# leg_controller.net
KiCad netlist of a schematic drawn in EAGLE
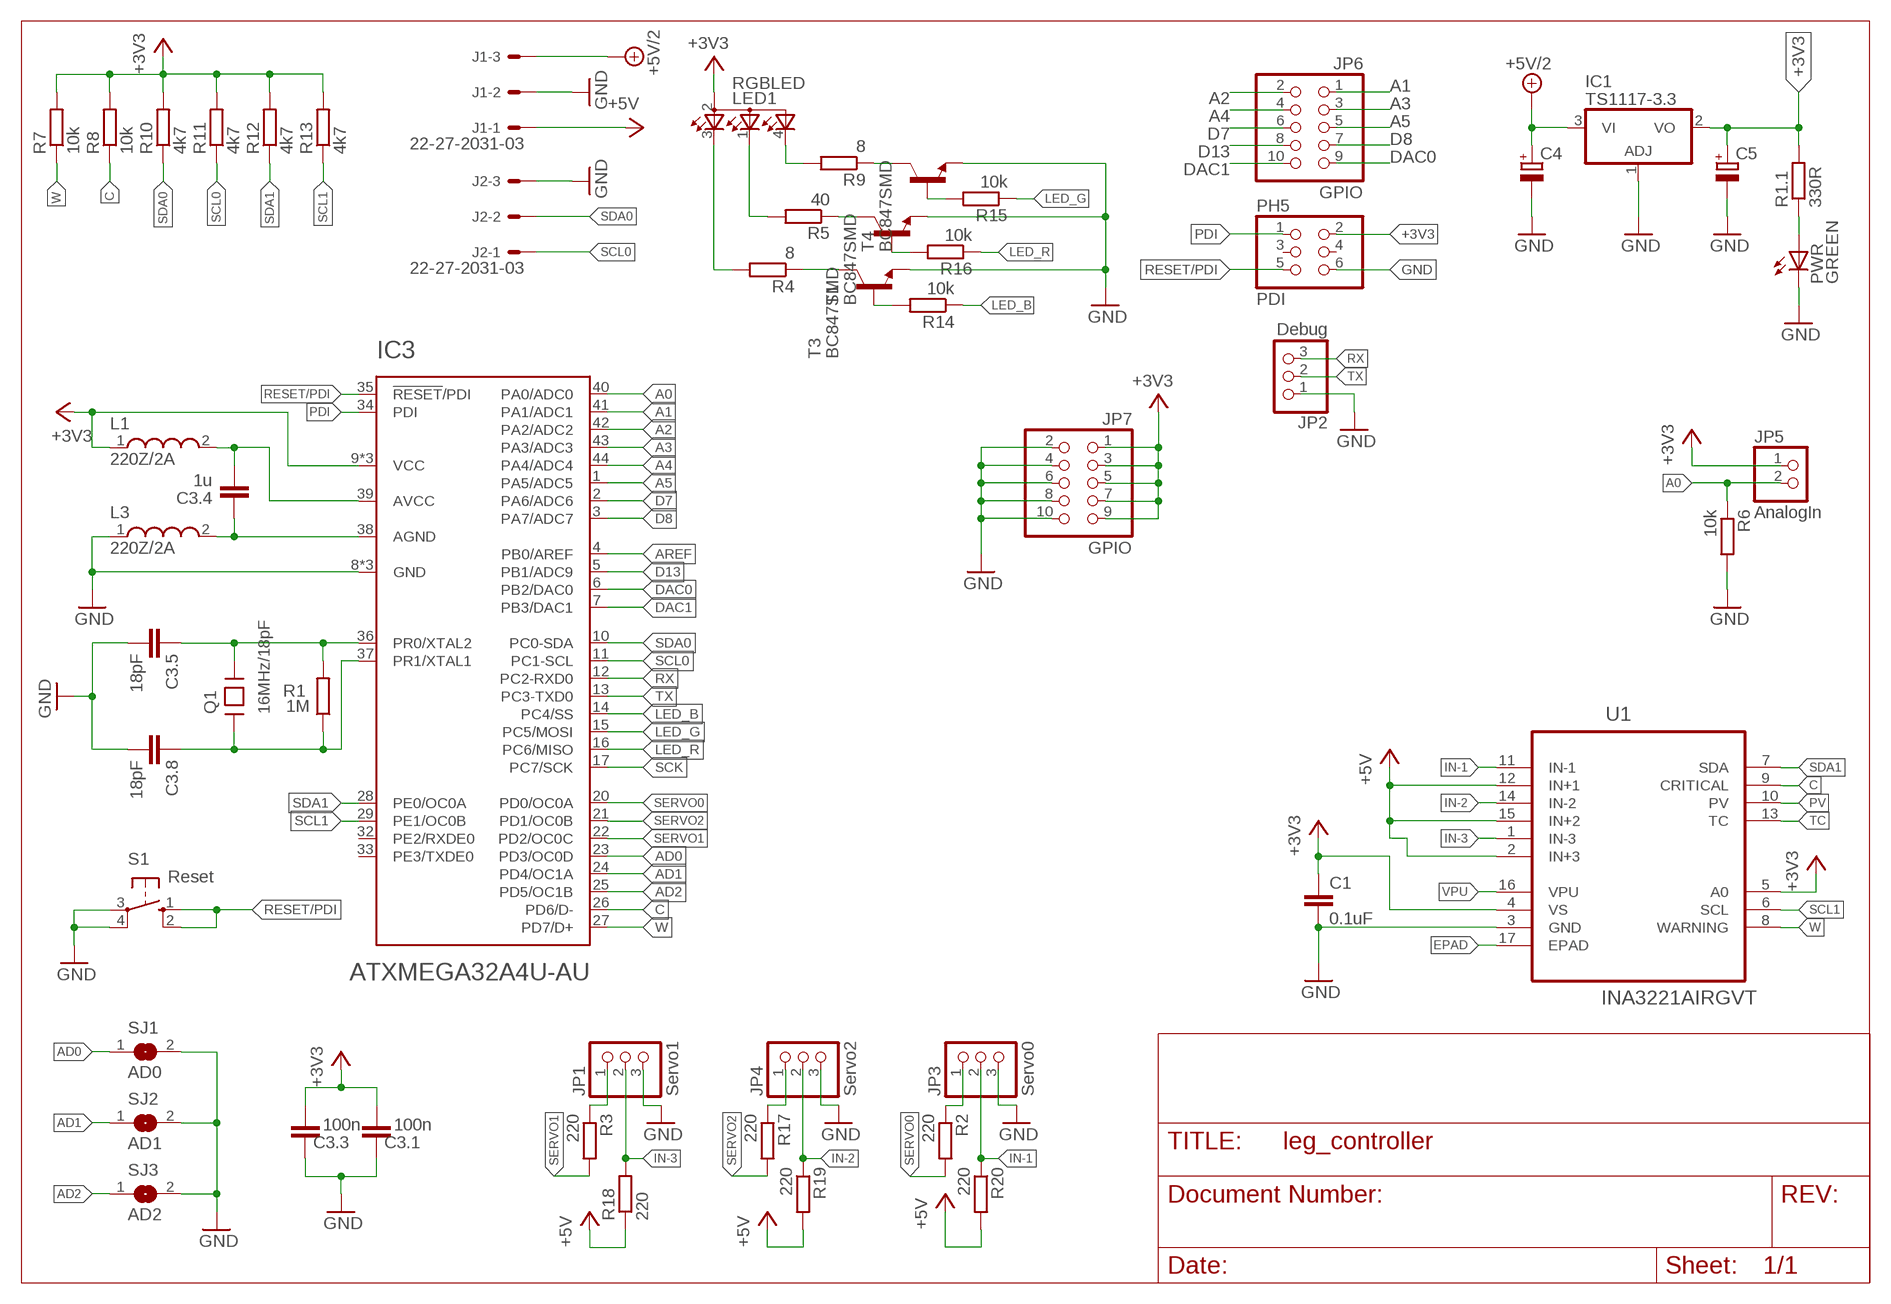
[diagram p0: schematic, sheet 1]

(export (version "E")
  (design (tool "Eeschema 10.0.6"))
  (components
    (comp (ref "C1")
      (value "0.1uF")
      (footprint "eagle-import:C0805")
      (libsource (lib "eagle-import") (part "C-EUC0805"))
    )
    (comp (ref "C3.1")
      (value "100n")
      (footprint "eagle-import:C0805K")
      (libsource (lib "eagle-import") (part "C-EUC0805K"))
    )
    (comp (ref "C3.3")
      (value "100n")
      (footprint "eagle-import:C0805K")
      (libsource (lib "eagle-import") (part "C-EUC0805K"))
    )
    (comp (ref "C3.4")
      (value "1u")
      (footprint "eagle-import:C0805K")
      (libsource (lib "eagle-import") (part "C-EUC0805K"))
    )
    (comp (ref "C3.5")
      (value "18pF")
      (footprint "eagle-import:C0805K")
      (libsource (lib "eagle-import") (part "C-EUC0805K"))
    )
    (comp (ref "C3.8")
      (value "18pF")
      (footprint "eagle-import:C0805K")
      (libsource (lib "eagle-import") (part "C-EUC0805K"))
    )
    (comp (ref "C4")
      (value "CPOL-EUSMCA")
      (footprint "eagle-import:SMC_A")
      (libsource (lib "eagle-import") (part "CPOL-EUSMCA"))
    )
    (comp (ref "C5")
      (value "CPOL-EUSMCA")
      (footprint "eagle-import:SMC_A")
      (libsource (lib "eagle-import") (part "CPOL-EUSMCA"))
    )
    (comp (ref "IC1")
      (value "TS1117-3.3")
      (footprint "eagle-import:DPACK")
      (libsource (lib "eagle-import") (part "MC33269?D-3.3"))
    )
    (comp (ref "IC3")
      (value "ATXMEGA32A4U-AU")
      (footprint "eagle-import:TQFP-44A-44")
      (libsource (lib "eagle-import") (part "ATXMEGA32A4U-AU"))
    )
    (comp (ref "J1")
      (value "22-27-2031-03")
      (footprint "eagle-import:6410-03")
      (libsource (lib "eagle-import") (part "22-?-0327-2031"))
    )
    (comp (ref "J2")
      (value "22-27-2031-03")
      (footprint "eagle-import:6410-03")
      (libsource (lib "eagle-import") (part "22-?-0327-2031"))
    )
    (comp (ref "JP1")
      (value "Servo1")
      (footprint "eagle-import:1X03")
      (libsource (lib "eagle-import") (part "PINHD-1X3"))
    )
    (comp (ref "JP2")
      (value "Debug")
      (footprint "eagle-import:1X03")
      (libsource (lib "eagle-import") (part "pinhead_NEW_PINHD-1X3"))
    )
    (comp (ref "JP3")
      (value "Servo0")
      (footprint "eagle-import:1X03")
      (libsource (lib "eagle-import") (part "PINHD-1X3"))
    )
    (comp (ref "JP4")
      (value "Servo2")
      (footprint "eagle-import:1X03")
      (libsource (lib "eagle-import") (part "PINHD-1X3"))
    )
    (comp (ref "JP5")
      (value "AnalogIn")
      (footprint "eagle-import:1X02")
      (libsource (lib "eagle-import") (part "PINHD-1X2"))
    )
    (comp (ref "JP6")
      (value "GPIO")
      (footprint "eagle-import:2X05")
      (libsource (lib "eagle-import") (part "PINHD-2X5"))
    )
    (comp (ref "JP7")
      (value "GPIO")
      (footprint "eagle-import:2X05")
      (libsource (lib "eagle-import") (part "PINHD-2X5"))
    )
    (comp (ref "L1")
      (value "220Z/2A")
      (footprint "eagle-import:WE-CBF_0805(W=3.0)")
      (libsource (lib "eagle-import") (part "WE-CBF_0805(WB/HS)"))
    )
    (comp (ref "L3")
      (value "220Z/2A")
      (footprint "eagle-import:WE-CBF_0805(W=3.0)")
      (libsource (lib "eagle-import") (part "WE-CBF_0805(WB/HS)"))
    )
    (comp (ref "LED1")
      (value "RGBLED")
      (footprint "eagle-import:P-LCC4-RGB")
      (libsource (lib "eagle-import") (part "RGBLED"))
    )
    (comp (ref "PH5")
      (value "PDI")
      (footprint "eagle-import:2X03")
      (libsource (lib "eagle-import") (part "PINHD-2X3"))
    )
    (comp (ref "PWR")
      (value "GREEN")
      (footprint "eagle-import:CHIP-LED0805")
      (libsource (lib "eagle-import") (part "LEDCHIP-LED0805"))
    )
    (comp (ref "Q1")
      (value "16MHz/18pF")
      (footprint "eagle-import:CRYSTAL-ABRACON-ABM3-SMD")
      (libsource (lib "eagle-import") (part "CRYSTAL-ABRACON-ABM3-SMD"))
    )
    (comp (ref "R1")
      (value "1M")
      (footprint "eagle-import:R0805")
      (libsource (lib "eagle-import") (part "R-EU_R0805"))
    )
    (comp (ref "R1.1")
      (value "330R")
      (footprint "eagle-import:R0805")
      (libsource (lib "eagle-import") (part "R-EU_R0805"))
    )
    (comp (ref "R2")
      (value "220")
      (footprint "eagle-import:R0805")
      (libsource (lib "eagle-import") (part "R-EU_R0805"))
    )
    (comp (ref "R3")
      (value "220")
      (footprint "eagle-import:R0805")
      (libsource (lib "eagle-import") (part "R-EU_R0805"))
    )
    (comp (ref "R4")
      (value "8")
      (footprint "eagle-import:R0805")
      (libsource (lib "eagle-import") (part "R-EU_R0805"))
    )
    (comp (ref "R5")
      (value "40")
      (footprint "eagle-import:R0805")
      (libsource (lib "eagle-import") (part "R-EU_R0805"))
    )
    (comp (ref "R6")
      (value "10k")
      (footprint "eagle-import:M0805")
      (libsource (lib "eagle-import") (part "R-EU_M0805"))
    )
    (comp (ref "R7")
      (value "10k")
      (footprint "eagle-import:R0805")
      (libsource (lib "eagle-import") (part "R-EU_R0805"))
    )
    (comp (ref "R8")
      (value "10k")
      (footprint "eagle-import:R0805")
      (libsource (lib "eagle-import") (part "R-EU_R0805"))
    )
    (comp (ref "R9")
      (value "8")
      (footprint "eagle-import:R0805")
      (libsource (lib "eagle-import") (part "R-EU_R0805"))
    )
    (comp (ref "R10")
      (value "4k7")
      (footprint "eagle-import:R0805")
      (libsource (lib "eagle-import") (part "R-EU_R0805"))
    )
    (comp (ref "R11")
      (value "4k7")
      (footprint "eagle-import:R0805")
      (libsource (lib "eagle-import") (part "R-EU_R0805"))
    )
    (comp (ref "R12")
      (value "4k7")
      (footprint "eagle-import:R0805")
      (libsource (lib "eagle-import") (part "R-EU_R0805"))
    )
    (comp (ref "R13")
      (value "4k7")
      (footprint "eagle-import:R0805")
      (libsource (lib "eagle-import") (part "R-EU_R0805"))
    )
    (comp (ref "R14")
      (value "10k")
      (footprint "eagle-import:R0805")
      (libsource (lib "eagle-import") (part "R-EU_R0805"))
    )
    (comp (ref "R15")
      (value "10k")
      (footprint "eagle-import:R0805")
      (libsource (lib "eagle-import") (part "R-EU_R0805"))
    )
    (comp (ref "R16")
      (value "10k")
      (footprint "eagle-import:R0805")
      (libsource (lib "eagle-import") (part "R-EU_R0805"))
    )
    (comp (ref "R17")
      (value "220")
      (footprint "eagle-import:R0805")
      (libsource (lib "eagle-import") (part "R-EU_R0805"))
    )
    (comp (ref "R18")
      (value "220")
      (footprint "eagle-import:R1206")
      (libsource (lib "eagle-import") (part "R-EU_R1206"))
    )
    (comp (ref "R19")
      (value "220")
      (footprint "eagle-import:R1206")
      (libsource (lib "eagle-import") (part "R-EU_R1206"))
    )
    (comp (ref "R20")
      (value "220")
      (footprint "eagle-import:R1206")
      (libsource (lib "eagle-import") (part "R-EU_R1206"))
    )
    (comp (ref "S1")
      (value "Reset")
      (footprint "eagle-import:B3F-10XX")
      (fields (field (name "MPN") "B3F-1000"))
      (libsource (lib "eagle-import") (part "10-XX"))
    )
    (comp (ref "SJ1")
      (value "AD0")
      (footprint "eagle-import:SJ")
      (libsource (lib "eagle-import") (part "SJ"))
    )
    (comp (ref "SJ2")
      (value "AD1")
      (footprint "eagle-import:SJ")
      (libsource (lib "eagle-import") (part "SJ"))
    )
    (comp (ref "SJ3")
      (value "AD2")
      (footprint "eagle-import:SJ")
      (libsource (lib "eagle-import") (part "SJ"))
    )
    (comp (ref "T1")
      (value "BC847SMD")
      (footprint "eagle-import:SOT23")
      (libsource (lib "eagle-import") (part "BC847SMD"))
    )
    (comp (ref "T3")
      (value "BC847SMD")
      (footprint "eagle-import:SOT23")
      (libsource (lib "eagle-import") (part "BC847SMD"))
    )
    (comp (ref "T4")
      (value "BC847SMD")
      (footprint "eagle-import:SOT23")
      (libsource (lib "eagle-import") (part "BC847SMD"))
    )
    (comp (ref "U1")
      (value "INA3221AIRGVT")
      (footprint "eagle-import:QFN65P400X400X80-17N")
      (libsource (lib "eagle-import") (part "INA3221AIRGVT"))
    )
  )
  (nets
    (net (code "1") (name "+3V3") (class "Default")
      (node (ref "C1") (pin "1") (pinfunction "1_1") (pintype "passive"))
      (node (ref "C3.1") (pin "1") (pinfunction "1_1") (pintype "passive"))
      (node (ref "C3.3") (pin "1") (pinfunction "1_1") (pintype "passive"))
      (node (ref "C5") (pin "+") (pinfunction "+_+") (pintype "passive"))
      (node (ref "IC1") (pin "2") (pinfunction "VO_2") (pintype "passive"))
      (node (ref "IC3") (pin "19") (pinfunction "VCC_19") (pintype "power_in"))
      (node (ref "IC3") (pin "31") (pinfunction "VCC_31") (pintype "power_in"))
      (node (ref "IC3") (pin "9") (pinfunction "VCC_9") (pintype "power_in"))
      (node (ref "JP5") (pin "1") (pinfunction "1_1") (pintype "passive"))
      (node (ref "JP7") (pin "1") (pinfunction "1_1") (pintype "passive"))
      (node (ref "JP7") (pin "3") (pinfunction "3_3") (pintype "passive"))
      (node (ref "JP7") (pin "5") (pinfunction "5_5") (pintype "passive"))
      (node (ref "JP7") (pin "7") (pinfunction "7_7") (pintype "passive"))
      (node (ref "JP7") (pin "9") (pinfunction "9_9") (pintype "passive"))
      (node (ref "L1") (pin "1") (pinfunction "1_1") (pintype "passive"))
      (node (ref "LED1") (pin "2") (pinfunction "A2_2") (pintype "passive"))
      (node (ref "PH5") (pin "2") (pinfunction "2_2") (pintype "passive"))
      (node (ref "R1.1") (pin "2") (pinfunction "2_2") (pintype "passive"))
      (node (ref "R10") (pin "2") (pinfunction "2_2") (pintype "passive"))
      (node (ref "R11") (pin "2") (pinfunction "2_2") (pintype "passive"))
      (node (ref "R12") (pin "2") (pinfunction "2_2") (pintype "passive"))
      (node (ref "R13") (pin "2") (pinfunction "2_2") (pintype "passive"))
      (node (ref "R7") (pin "2") (pinfunction "2_2") (pintype "passive"))
      (node (ref "R8") (pin "2") (pinfunction "2_2") (pintype "passive"))
      (node (ref "U1") (pin "4") (pinfunction "VS_4") (pintype "power_in"))
      (node (ref "U1") (pin "5") (pinfunction "A0_5") (pintype "input"))
    )
    (net (code "2") (name "+5V") (class "Default")
      (node (ref "J1") (pin "1") (pinfunction "S_1") (pintype "passive"))
      (node (ref "R18") (pin "1") (pinfunction "1_1") (pintype "passive"))
      (node (ref "R19") (pin "2") (pinfunction "2_2") (pintype "passive"))
      (node (ref "R20") (pin "2") (pinfunction "2_2") (pintype "passive"))
      (node (ref "U1") (pin "12") (pinfunction "IN+1_12") (pintype "input"))
      (node (ref "U1") (pin "15") (pinfunction "IN+2_15") (pintype "input"))
      (node (ref "U1") (pin "2") (pinfunction "IN+3_2") (pintype "input"))
    )
    (net (code "3") (name "+5V{slash}2") (class "Default")
      (node (ref "C4") (pin "+") (pinfunction "+_+") (pintype "passive"))
      (node (ref "IC1") (pin "3") (pinfunction "VI_3") (pintype "input"))
      (node (ref "J1") (pin "3") (pinfunction "S_3") (pintype "passive"))
    )
    (net (code "4") (name "A0") (class "Default")
      (node (ref "IC3") (pin "40") (pinfunction "PA0/ADC0_40") (pintype "bidirectional"))
      (node (ref "JP5") (pin "2") (pinfunction "2_2") (pintype "passive"))
      (node (ref "R6") (pin "1") (pinfunction "1_1") (pintype "passive"))
    )
    (net (code "5") (name "A1") (class "Default")
      (node (ref "IC3") (pin "41") (pinfunction "PA1/ADC1_41") (pintype "bidirectional"))
      (node (ref "JP6") (pin "1") (pinfunction "1_1") (pintype "passive"))
    )
    (net (code "6") (name "A2") (class "Default")
      (node (ref "IC3") (pin "42") (pinfunction "PA2/ADC2_42") (pintype "bidirectional"))
      (node (ref "JP6") (pin "2") (pinfunction "2_2") (pintype "passive"))
    )
    (net (code "7") (name "A3") (class "Default")
      (node (ref "IC3") (pin "43") (pinfunction "PA3/ADC3_43") (pintype "bidirectional"))
      (node (ref "JP6") (pin "3") (pinfunction "3_3") (pintype "passive"))
    )
    (net (code "8") (name "A4") (class "Default")
      (node (ref "IC3") (pin "44") (pinfunction "PA4/ADC4_44") (pintype "bidirectional"))
      (node (ref "JP6") (pin "4") (pinfunction "4_4") (pintype "passive"))
    )
    (net (code "9") (name "A5") (class "Default")
      (node (ref "IC3") (pin "1") (pinfunction "PA5/ADC5_1") (pintype "bidirectional"))
      (node (ref "JP6") (pin "5") (pinfunction "5_5") (pintype "passive"))
    )
    (net (code "10") (name "AD0") (class "Default")
      (node (ref "IC3") (pin "23") (pinfunction "PD3/OC0D_23") (pintype "bidirectional"))
      (node (ref "SJ1") (pin "1") (pinfunction "1_1") (pintype "passive"))
    )
    (net (code "11") (name "AD1") (class "Default")
      (node (ref "IC3") (pin "24") (pinfunction "PD4/OC1A_24") (pintype "bidirectional"))
      (node (ref "SJ2") (pin "1") (pinfunction "1_1") (pintype "passive"))
    )
    (net (code "12") (name "AD2") (class "Default")
      (node (ref "IC3") (pin "25") (pinfunction "PD5/OC1B_25") (pintype "bidirectional"))
      (node (ref "SJ3") (pin "1") (pinfunction "1_1") (pintype "passive"))
    )
    (net (code "13") (name "AREF") (class "Default")
      (node (ref "IC3") (pin "4") (pinfunction "PB0/AREF_4") (pintype "bidirectional"))
    )
    (net (code "14") (name "C") (class "Default")
      (node (ref "IC3") (pin "26") (pinfunction "PD6/D-_26") (pintype "bidirectional"))
      (node (ref "R8") (pin "1") (pinfunction "1_1") (pintype "passive"))
      (node (ref "U1") (pin "9") (pinfunction "CRITICAL_9") (pintype "output"))
    )
    (net (code "15") (name "D7") (class "Default")
      (node (ref "IC3") (pin "2") (pinfunction "PA6/ADC6_2") (pintype "bidirectional"))
      (node (ref "JP6") (pin "6") (pinfunction "6_6") (pintype "passive"))
    )
    (net (code "16") (name "D8") (class "Default")
      (node (ref "IC3") (pin "3") (pinfunction "PA7/ADC7_3") (pintype "bidirectional"))
      (node (ref "JP6") (pin "7") (pinfunction "7_7") (pintype "passive"))
    )
    (net (code "17") (name "D13") (class "Default")
      (node (ref "IC3") (pin "5") (pinfunction "PB1/ADC9_5") (pintype "bidirectional"))
      (node (ref "JP6") (pin "8") (pinfunction "8_8") (pintype "passive"))
    )
    (net (code "18") (name "DAC0") (class "Default")
      (node (ref "IC3") (pin "6") (pinfunction "PB2/DAC0_6") (pintype "bidirectional"))
      (node (ref "JP6") (pin "9") (pinfunction "9_9") (pintype "passive"))
    )
    (net (code "19") (name "DAC1") (class "Default")
      (node (ref "IC3") (pin "7") (pinfunction "PB3/DAC1_7") (pintype "bidirectional"))
      (node (ref "JP6") (pin "10") (pinfunction "10_10") (pintype "passive"))
    )
    (net (code "20") (name "EPAD") (class "Default")
      (node (ref "U1") (pin "17") (pinfunction "EPAD_17") (pintype "passive"))
    )
    (net (code "21") (name "GND") (class "Default")
      (node (ref "C1") (pin "2") (pinfunction "2_2") (pintype "passive"))
      (node (ref "C3.1") (pin "2") (pinfunction "2_2") (pintype "passive"))
      (node (ref "C3.3") (pin "2") (pinfunction "2_2") (pintype "passive"))
      (node (ref "C3.5") (pin "2") (pinfunction "2_2") (pintype "passive"))
      (node (ref "C3.8") (pin "2") (pinfunction "2_2") (pintype "passive"))
      (node (ref "C4") (pin "-") (pinfunction "-_-") (pintype "passive"))
      (node (ref "C5") (pin "-") (pinfunction "-_-") (pintype "passive"))
      (node (ref "IC1") (pin "1") (pinfunction "ADJ_1") (pintype "input"))
      (node (ref "IC3") (pin "18") (pinfunction "GND_18") (pintype "power_in"))
      (node (ref "IC3") (pin "30") (pinfunction "GND_30") (pintype "power_in"))
      (node (ref "IC3") (pin "8") (pinfunction "GND_8") (pintype "power_in"))
      (node (ref "J1") (pin "2") (pinfunction "S_2") (pintype "passive"))
      (node (ref "J2") (pin "3") (pinfunction "S_3") (pintype "passive"))
      (node (ref "JP1") (pin "3") (pinfunction "3_3") (pintype "passive"))
      (node (ref "JP2") (pin "1") (pinfunction "1_1") (pintype "passive"))
      (node (ref "JP3") (pin "3") (pinfunction "3_3") (pintype "passive"))
      (node (ref "JP4") (pin "3") (pinfunction "3_3") (pintype "passive"))
      (node (ref "JP7") (pin "10") (pinfunction "10_10") (pintype "passive"))
      (node (ref "JP7") (pin "2") (pinfunction "2_2") (pintype "passive"))
      (node (ref "JP7") (pin "4") (pinfunction "4_4") (pintype "passive"))
      (node (ref "JP7") (pin "6") (pinfunction "6_6") (pintype "passive"))
      (node (ref "JP7") (pin "8") (pinfunction "8_8") (pintype "passive"))
      (node (ref "L3") (pin "1") (pinfunction "1_1") (pintype "passive"))
      (node (ref "PH5") (pin "6") (pinfunction "6_6") (pintype "passive"))
      (node (ref "PWR") (pin "C") (pinfunction "C_C") (pintype "passive"))
      (node (ref "R6") (pin "2") (pinfunction "2_2") (pintype "passive"))
      (node (ref "S1") (pin "3") (pinfunction "P_3") (pintype "passive"))
      (node (ref "S1") (pin "4") (pinfunction "P1_4") (pintype "passive"))
      (node (ref "SJ1") (pin "2") (pinfunction "2_2") (pintype "passive"))
      (node (ref "SJ2") (pin "2") (pinfunction "2_2") (pintype "passive"))
      (node (ref "SJ3") (pin "2") (pinfunction "2_2") (pintype "passive"))
      (node (ref "T1") (pin "2") (pinfunction "E_2") (pintype "passive"))
      (node (ref "T3") (pin "2") (pinfunction "E_2") (pintype "passive"))
      (node (ref "T4") (pin "2") (pinfunction "E_2") (pintype "passive"))
      (node (ref "U1") (pin "3") (pinfunction "GND_3") (pintype "passive"))
    )
    (net (code "22") (name "IN-1") (class "Default")
      (node (ref "JP3") (pin "2") (pinfunction "2_2") (pintype "passive"))
      (node (ref "R20") (pin "1") (pinfunction "1_1") (pintype "passive"))
      (node (ref "U1") (pin "11") (pinfunction "IN-1_11") (pintype "input"))
    )
    (net (code "23") (name "IN-2") (class "Default")
      (node (ref "JP4") (pin "2") (pinfunction "2_2") (pintype "passive"))
      (node (ref "R19") (pin "1") (pinfunction "1_1") (pintype "passive"))
      (node (ref "U1") (pin "14") (pinfunction "IN-2_14") (pintype "input"))
    )
    (net (code "24") (name "IN-3") (class "Default")
      (node (ref "JP1") (pin "2") (pinfunction "2_2") (pintype "passive"))
      (node (ref "R18") (pin "2") (pinfunction "2_2") (pintype "passive"))
      (node (ref "U1") (pin "1") (pinfunction "IN-3_1") (pintype "input"))
    )
    (net (code "25") (name "LED_B") (class "Default")
      (node (ref "IC3") (pin "14") (pinfunction "PC4/SS_14") (pintype "bidirectional"))
      (node (ref "R14") (pin "1") (pinfunction "1_1") (pintype "passive"))
    )
    (net (code "26") (name "LED_G") (class "Default")
      (node (ref "IC3") (pin "15") (pinfunction "PC5/MOSI_15") (pintype "bidirectional"))
      (node (ref "R15") (pin "1") (pinfunction "1_1") (pintype "passive"))
    )
    (net (code "27") (name "LED_R") (class "Default")
      (node (ref "IC3") (pin "16") (pinfunction "PC6/MISO_16") (pintype "bidirectional"))
      (node (ref "R16") (pin "1") (pinfunction "1_1") (pintype "passive"))
    )
    (net (code "28") (name "Net-(IC3-AGND)") (class "Default")
      (node (ref "C3.4") (pin "2") (pinfunction "2_2") (pintype "passive"))
      (node (ref "IC3") (pin "38") (pinfunction "AGND_38") (pintype "power_in"))
      (node (ref "L3") (pin "2") (pinfunction "2_2") (pintype "passive"))
    )
    (net (code "29") (name "Net-(IC3-AVCC)") (class "Default")
      (node (ref "C3.4") (pin "1") (pinfunction "1_1") (pintype "passive"))
      (node (ref "IC3") (pin "39") (pinfunction "AVCC_39") (pintype "power_in"))
      (node (ref "L1") (pin "2") (pinfunction "2_2") (pintype "passive"))
    )
    (net (code "30") (name "Net-(IC3-PR0{slash}XTAL2)") (class "Default")
      (node (ref "C3.5") (pin "1") (pinfunction "1_1") (pintype "passive"))
      (node (ref "IC3") (pin "36") (pinfunction "PR0/XTAL2_36") (pintype "bidirectional"))
      (node (ref "Q1") (pin "P$2") (pinfunction "P$2_P$2") (pintype "bidirectional"))
      (node (ref "R1") (pin "2") (pinfunction "2_2") (pintype "passive"))
    )
    (net (code "31") (name "Net-(IC3-PR1{slash}XTAL1)") (class "Default")
      (node (ref "C3.8") (pin "1") (pinfunction "1_1") (pintype "passive"))
      (node (ref "IC3") (pin "37") (pinfunction "PR1/XTAL1_37") (pintype "bidirectional"))
      (node (ref "Q1") (pin "P$1") (pinfunction "P$1_P$1") (pintype "bidirectional"))
      (node (ref "R1") (pin "1") (pinfunction "1_1") (pintype "passive"))
    )
    (net (code "32") (name "Net-(JP1-Pad1)") (class "Default")
      (node (ref "JP1") (pin "1") (pinfunction "1_1") (pintype "passive"))
      (node (ref "R3") (pin "1") (pinfunction "1_1") (pintype "passive"))
    )
    (net (code "33") (name "Net-(JP3-Pad1)") (class "Default")
      (node (ref "JP3") (pin "1") (pinfunction "1_1") (pintype "passive"))
      (node (ref "R2") (pin "1") (pinfunction "1_1") (pintype "passive"))
    )
    (net (code "34") (name "Net-(JP4-Pad1)") (class "Default")
      (node (ref "JP4") (pin "1") (pinfunction "1_1") (pintype "passive"))
      (node (ref "R17") (pin "1") (pinfunction "1_1") (pintype "passive"))
    )
    (net (code "35") (name "Net-(LED1-CBLUE)") (class "Default")
      (node (ref "LED1") (pin "1") (pinfunction "CBLUE_1") (pintype "passive"))
      (node (ref "R5") (pin "2") (pinfunction "2_2") (pintype "passive"))
    )
    (net (code "36") (name "Net-(LED1-CGREEN)") (class "Default")
      (node (ref "LED1") (pin "4") (pinfunction "CGREEN_4") (pintype "passive"))
      (node (ref "R9") (pin "2") (pinfunction "2_2") (pintype "passive"))
    )
    (net (code "37") (name "Net-(LED1-CRED)") (class "Default")
      (node (ref "LED1") (pin "3") (pinfunction "CRED_3") (pintype "passive"))
      (node (ref "R4") (pin "2") (pinfunction "2_2") (pintype "passive"))
    )
    (net (code "38") (name "Net-(PWR-PadA)") (class "Default")
      (node (ref "PWR") (pin "A") (pinfunction "A_A") (pintype "passive"))
      (node (ref "R1.1") (pin "1") (pinfunction "1_1") (pintype "passive"))
    )
    (net (code "39") (name "Net-(T1-B)") (class "Default")
      (node (ref "R16") (pin "2") (pinfunction "2_2") (pintype "passive"))
      (node (ref "T1") (pin "1") (pinfunction "B_1") (pintype "passive"))
    )
    (net (code "40") (name "Net-(T1-C)") (class "Default")
      (node (ref "R5") (pin "1") (pinfunction "1_1") (pintype "passive"))
      (node (ref "T1") (pin "3") (pinfunction "C_3") (pintype "passive"))
    )
    (net (code "41") (name "Net-(T3-B)") (class "Default")
      (node (ref "R14") (pin "2") (pinfunction "2_2") (pintype "passive"))
      (node (ref "T3") (pin "1") (pinfunction "B_1") (pintype "passive"))
    )
    (net (code "42") (name "Net-(T3-C)") (class "Default")
      (node (ref "R4") (pin "1") (pinfunction "1_1") (pintype "passive"))
      (node (ref "T3") (pin "3") (pinfunction "C_3") (pintype "passive"))
    )
    (net (code "43") (name "Net-(T4-B)") (class "Default")
      (node (ref "R15") (pin "2") (pinfunction "2_2") (pintype "passive"))
      (node (ref "T4") (pin "1") (pinfunction "B_1") (pintype "passive"))
    )
    (net (code "44") (name "Net-(T4-C)") (class "Default")
      (node (ref "R9") (pin "1") (pinfunction "1_1") (pintype "passive"))
      (node (ref "T4") (pin "3") (pinfunction "C_3") (pintype "passive"))
    )
    (net (code "45") (name "PDI") (class "Default")
      (node (ref "IC3") (pin "34") (pinfunction "PDI_34") (pintype "bidirectional"))
      (node (ref "PH5") (pin "1") (pinfunction "1_1") (pintype "passive"))
    )
    (net (code "46") (name "PV") (class "Default")
      (node (ref "U1") (pin "10") (pinfunction "PV_10") (pintype "output"))
    )
    (net (code "47") (name "RESET{slash}PDI") (class "Default")
      (node (ref "IC3") (pin "35") (pinfunction "~{RESET}/PDI_35") (pintype "bidirectional"))
      (node (ref "PH5") (pin "5") (pinfunction "5_5") (pintype "passive"))
      (node (ref "S1") (pin "1") (pinfunction "S_1") (pintype "passive"))
      (node (ref "S1") (pin "2") (pinfunction "S1_2") (pintype "passive"))
    )
    (net (code "48") (name "RX") (class "Default")
      (node (ref "IC3") (pin "12") (pinfunction "PC2-RXD0_12") (pintype "bidirectional"))
      (node (ref "JP2") (pin "3") (pinfunction "3_3") (pintype "passive"))
    )
    (net (code "49") (name "SCK") (class "Default")
      (node (ref "IC3") (pin "17") (pinfunction "PC7/SCK_17") (pintype "bidirectional"))
    )
    (net (code "50") (name "SCL0") (class "Default")
      (node (ref "IC3") (pin "11") (pinfunction "PC1-SCL_11") (pintype "bidirectional"))
      (node (ref "J2") (pin "1") (pinfunction "S_1") (pintype "passive"))
      (node (ref "R11") (pin "1") (pinfunction "1_1") (pintype "passive"))
    )
    (net (code "51") (name "SCL1") (class "Default")
      (node (ref "IC3") (pin "29") (pinfunction "PE1/OC0B_29") (pintype "bidirectional"))
      (node (ref "R13") (pin "1") (pinfunction "1_1") (pintype "passive"))
      (node (ref "U1") (pin "6") (pinfunction "SCL_6") (pintype "input"))
    )
    (net (code "52") (name "SDA0") (class "Default")
      (node (ref "IC3") (pin "10") (pinfunction "PC0-SDA_10") (pintype "bidirectional"))
      (node (ref "J2") (pin "2") (pinfunction "S_2") (pintype "passive"))
      (node (ref "R10") (pin "1") (pinfunction "1_1") (pintype "passive"))
    )
    (net (code "53") (name "SDA1") (class "Default")
      (node (ref "IC3") (pin "28") (pinfunction "PE0/OC0A_28") (pintype "bidirectional"))
      (node (ref "R12") (pin "1") (pinfunction "1_1") (pintype "passive"))
      (node (ref "U1") (pin "7") (pinfunction "SDA_7") (pintype "bidirectional"))
    )
    (net (code "54") (name "SERVO0") (class "Default")
      (node (ref "IC3") (pin "20") (pinfunction "PD0/OC0A_20") (pintype "bidirectional"))
      (node (ref "R2") (pin "2") (pinfunction "2_2") (pintype "passive"))
    )
    (net (code "55") (name "SERVO1") (class "Default")
      (node (ref "IC3") (pin "22") (pinfunction "PD2/OC0C_22") (pintype "bidirectional"))
      (node (ref "R3") (pin "2") (pinfunction "2_2") (pintype "passive"))
    )
    (net (code "56") (name "SERVO2") (class "Default")
      (node (ref "IC3") (pin "21") (pinfunction "PD1/OC0B_21") (pintype "bidirectional"))
      (node (ref "R17") (pin "2") (pinfunction "2_2") (pintype "passive"))
    )
    (net (code "57") (name "TC") (class "Default")
      (node (ref "U1") (pin "13") (pinfunction "TC_13") (pintype "output"))
    )
    (net (code "58") (name "TX") (class "Default")
      (node (ref "IC3") (pin "13") (pinfunction "PC3-TXD0_13") (pintype "bidirectional"))
      (node (ref "JP2") (pin "2") (pinfunction "2_2") (pintype "passive"))
    )
    (net (code "59") (name "VPU") (class "Default")
      (node (ref "U1") (pin "16") (pinfunction "VPU_16") (pintype "power_in"))
    )
    (net (code "60") (name "W") (class "Default")
      (node (ref "IC3") (pin "27") (pinfunction "PD7/D+_27") (pintype "bidirectional"))
      (node (ref "R7") (pin "1") (pinfunction "1_1") (pintype "passive"))
      (node (ref "U1") (pin "8") (pinfunction "WARNING_8") (pintype "output"))
    )
    (net (code "61") (name "unconnected-(IC3-PE2{slash}RXDE0-Pad32)") (class "Default")
      (node (ref "IC3") (pin "32") (pinfunction "PE2/RXDE0_32") (pintype "bidirectional"))
    )
    (net (code "62") (name "unconnected-(IC3-PE3{slash}TXDE0-Pad33)") (class "Default")
      (node (ref "IC3") (pin "33") (pinfunction "PE3/TXDE0_33") (pintype "bidirectional"))
    )
    (net (code "63") (name "unconnected-(PH5-Pad3)") (class "Default")
      (node (ref "PH5") (pin "3") (pinfunction "3_3") (pintype "passive"))
    )
    (net (code "64") (name "unconnected-(PH5-Pad4)") (class "Default")
      (node (ref "PH5") (pin "4") (pinfunction "4_4") (pintype "passive"))
    )
  )
)
